# TA_2_DONG.net
KiCad netlist of a schematic drawn in EAGLE
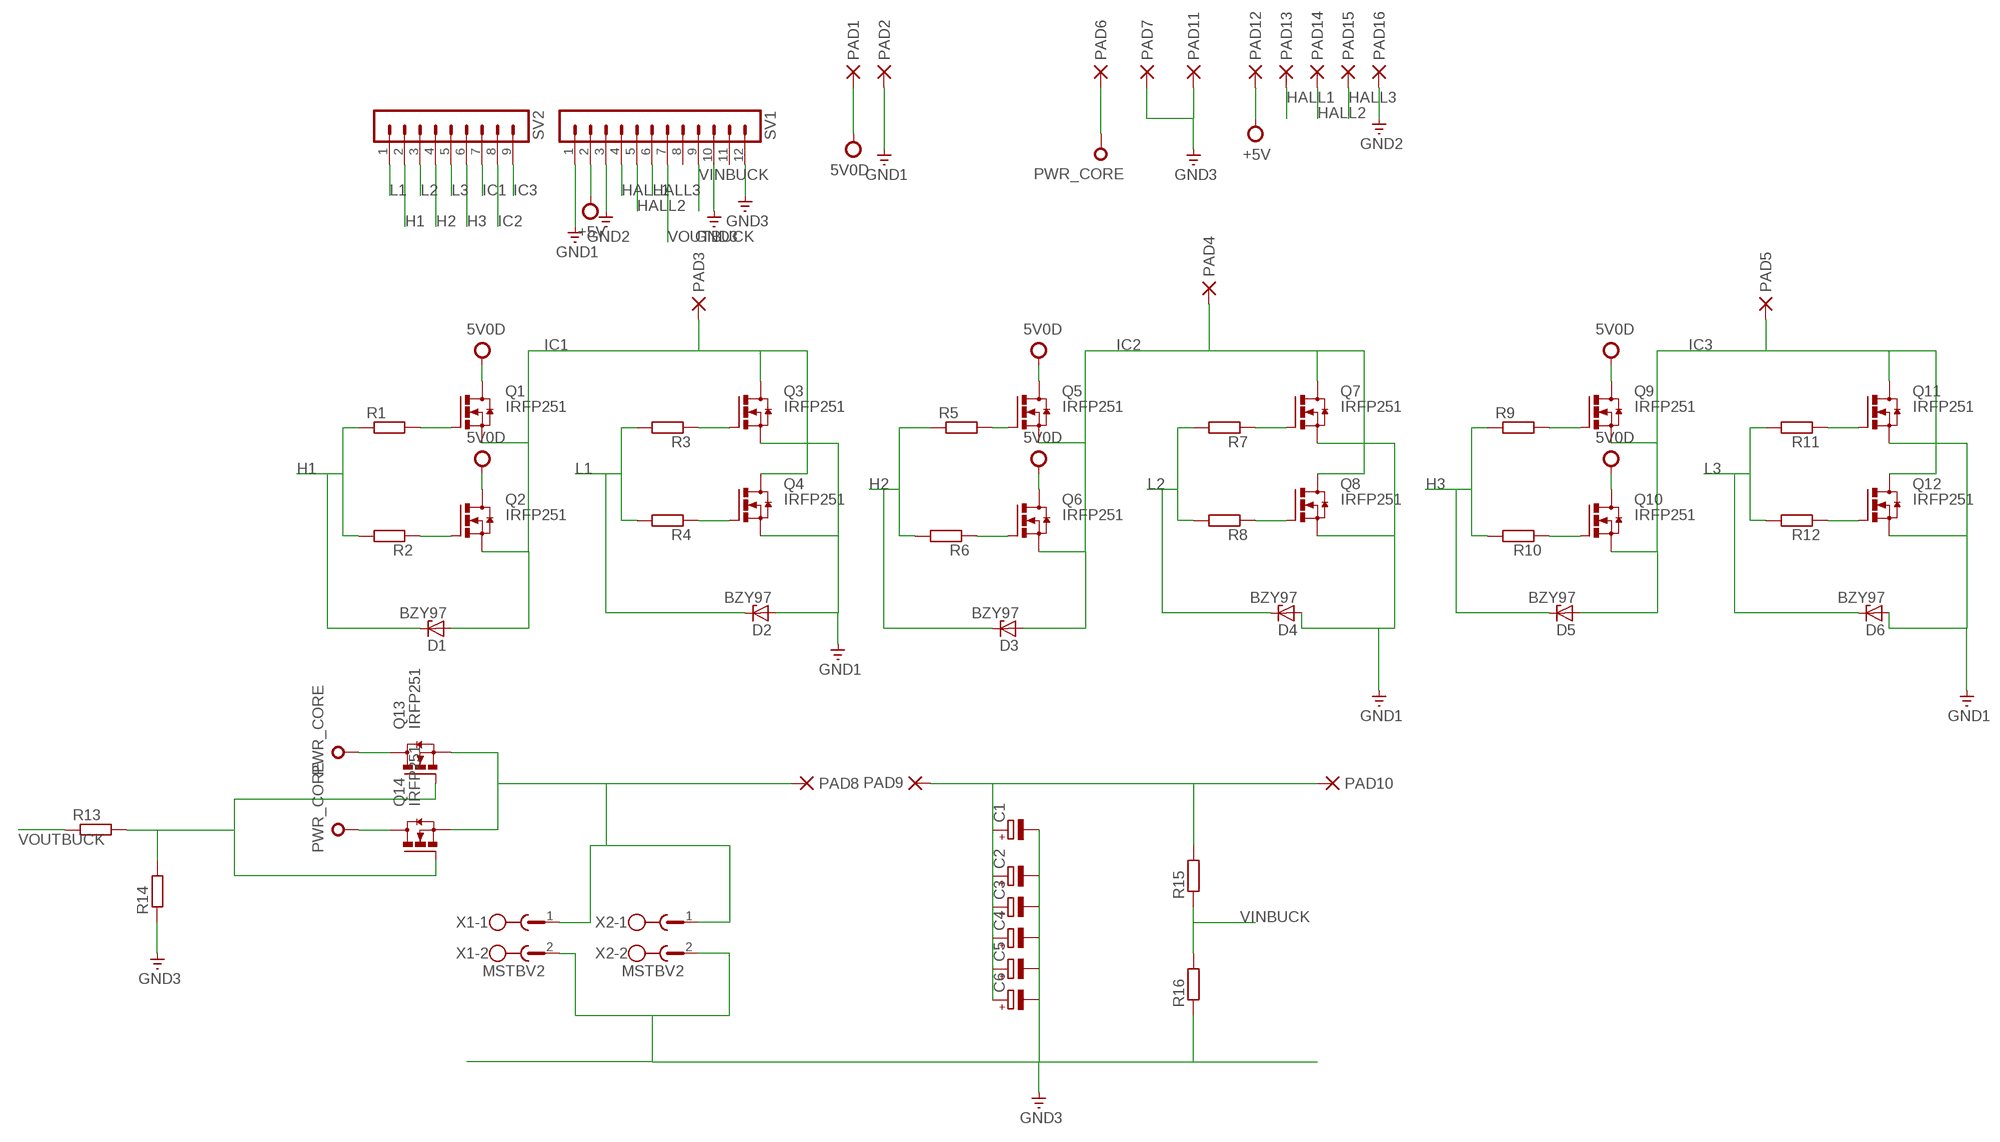
[diagram p0: schematic, sheet 1]

(export (version "E")
  (design (tool "Eeschema 10.0.6"))
  (components
    (comp (ref "C1")
      (value "CPOL-EUTT5D9")
      (footprint "eagle-import:TT5D9")
      (libsource (lib "eagle-import") (part "CPOL-EUTT5D9"))
    )
    (comp (ref "C2")
      (value "CPOL-EUTT5D9")
      (footprint "eagle-import:TT5D9")
      (libsource (lib "eagle-import") (part "CPOL-EUTT5D9"))
    )
    (comp (ref "C3")
      (value "CPOL-EUTT5D9")
      (footprint "eagle-import:TT5D9")
      (libsource (lib "eagle-import") (part "CPOL-EUTT5D9"))
    )
    (comp (ref "C4")
      (value "CPOL-EUTT5D9")
      (footprint "eagle-import:TT5D9")
      (libsource (lib "eagle-import") (part "CPOL-EUTT5D9"))
    )
    (comp (ref "C5")
      (value "CPOL-EUTT5D9")
      (footprint "eagle-import:TT5D9")
      (libsource (lib "eagle-import") (part "CPOL-EUTT5D9"))
    )
    (comp (ref "C6")
      (value "CPOL-EUTT5D9")
      (footprint "eagle-import:TT5D9")
      (libsource (lib "eagle-import") (part "CPOL-EUTT5D9"))
    )
    (comp (ref "D1")
      (value "BZY97")
      (footprint "eagle-import:F126Z12")
      (libsource (lib "eagle-import") (part "BZY97"))
    )
    (comp (ref "D2")
      (value "BZY97")
      (footprint "eagle-import:F126Z12")
      (libsource (lib "eagle-import") (part "BZY97"))
    )
    (comp (ref "D3")
      (value "BZY97")
      (footprint "eagle-import:F126Z12")
      (libsource (lib "eagle-import") (part "BZY97"))
    )
    (comp (ref "D4")
      (value "BZY97")
      (footprint "eagle-import:F126Z12")
      (libsource (lib "eagle-import") (part "BZY97"))
    )
    (comp (ref "D5")
      (value "BZY97")
      (footprint "eagle-import:F126Z12")
      (libsource (lib "eagle-import") (part "BZY97"))
    )
    (comp (ref "D6")
      (value "BZY97")
      (footprint "eagle-import:F126Z12")
      (libsource (lib "eagle-import") (part "BZY97"))
    )
    (comp (ref "PAD1")
      (value "PAD-0820")
      (footprint "eagle-import:0820")
      (libsource (lib "eagle-import") (part "PAD-0820"))
    )
    (comp (ref "PAD2")
      (value "PAD-0820")
      (footprint "eagle-import:0820")
      (libsource (lib "eagle-import") (part "PAD-0820"))
    )
    (comp (ref "PAD3")
      (value "PAD-0820")
      (footprint "eagle-import:0820")
      (libsource (lib "eagle-import") (part "PAD-0820"))
    )
    (comp (ref "PAD4")
      (value "PAD-0820")
      (footprint "eagle-import:0820")
      (libsource (lib "eagle-import") (part "PAD-0820"))
    )
    (comp (ref "PAD5")
      (value "PAD-0820")
      (footprint "eagle-import:0820")
      (libsource (lib "eagle-import") (part "PAD-0820"))
    )
    (comp (ref "PAD6")
      (value "PAD-0820")
      (footprint "eagle-import:0820")
      (libsource (lib "eagle-import") (part "PAD-0820"))
    )
    (comp (ref "PAD7")
      (value "PAD-0820")
      (footprint "eagle-import:0820")
      (libsource (lib "eagle-import") (part "PAD-0820"))
    )
    (comp (ref "PAD8")
      (value "PAD-0820")
      (footprint "eagle-import:0820")
      (libsource (lib "eagle-import") (part "PAD-0820"))
    )
    (comp (ref "PAD9")
      (value "PAD-0820")
      (footprint "eagle-import:0820")
      (libsource (lib "eagle-import") (part "PAD-0820"))
    )
    (comp (ref "PAD10")
      (value "PAD-0820")
      (footprint "eagle-import:0820")
      (libsource (lib "eagle-import") (part "PAD-0820"))
    )
    (comp (ref "PAD11")
      (value "PAD-0820")
      (footprint "eagle-import:0820")
      (libsource (lib "eagle-import") (part "PAD-0820"))
    )
    (comp (ref "PAD12")
      (value "PAD-0820")
      (footprint "eagle-import:0820")
      (libsource (lib "eagle-import") (part "PAD-0820"))
    )
    (comp (ref "PAD13")
      (value "PAD-0820")
      (footprint "eagle-import:0820")
      (libsource (lib "eagle-import") (part "PAD-0820"))
    )
    (comp (ref "PAD14")
      (value "PAD-0820")
      (footprint "eagle-import:0820")
      (libsource (lib "eagle-import") (part "PAD-0820"))
    )
    (comp (ref "PAD15")
      (value "PAD-0820")
      (footprint "eagle-import:0820")
      (libsource (lib "eagle-import") (part "PAD-0820"))
    )
    (comp (ref "PAD16")
      (value "PAD-0820")
      (footprint "eagle-import:0820")
      (libsource (lib "eagle-import") (part "PAD-0820"))
    )
    (comp (ref "Q1")
      (value "IRFP251")
      (footprint "eagle-import:TO-247AD-V")
      (libsource (lib "eagle-import") (part "IRFP251"))
    )
    (comp (ref "Q2")
      (value "IRFP251")
      (footprint "eagle-import:TO-247AD-V")
      (libsource (lib "eagle-import") (part "IRFP251"))
    )
    (comp (ref "Q3")
      (value "IRFP251")
      (footprint "eagle-import:TO-247AD-V")
      (libsource (lib "eagle-import") (part "IRFP251"))
    )
    (comp (ref "Q4")
      (value "IRFP251")
      (footprint "eagle-import:TO-247AD-V")
      (libsource (lib "eagle-import") (part "IRFP251"))
    )
    (comp (ref "Q5")
      (value "IRFP251")
      (footprint "eagle-import:TO-247AD-V")
      (libsource (lib "eagle-import") (part "IRFP251"))
    )
    (comp (ref "Q6")
      (value "IRFP251")
      (footprint "eagle-import:TO-247AD-V")
      (libsource (lib "eagle-import") (part "IRFP251"))
    )
    (comp (ref "Q7")
      (value "IRFP251")
      (footprint "eagle-import:TO-247AD-V")
      (libsource (lib "eagle-import") (part "IRFP251"))
    )
    (comp (ref "Q8")
      (value "IRFP251")
      (footprint "eagle-import:TO-247AD-V")
      (libsource (lib "eagle-import") (part "IRFP251"))
    )
    (comp (ref "Q9")
      (value "IRFP251")
      (footprint "eagle-import:TO-247AD-V")
      (libsource (lib "eagle-import") (part "IRFP251"))
    )
    (comp (ref "Q10")
      (value "IRFP251")
      (footprint "eagle-import:TO-247AD-V")
      (libsource (lib "eagle-import") (part "IRFP251"))
    )
    (comp (ref "Q11")
      (value "IRFP251")
      (footprint "eagle-import:TO-247AD-V")
      (libsource (lib "eagle-import") (part "IRFP251"))
    )
    (comp (ref "Q12")
      (value "IRFP251")
      (footprint "eagle-import:TO-247AD-V")
      (libsource (lib "eagle-import") (part "IRFP251"))
    )
    (comp (ref "Q13")
      (value "IRFP251")
      (footprint "eagle-import:TO-247AD-V")
      (libsource (lib "eagle-import") (part "IRFP251"))
    )
    (comp (ref "Q14")
      (value "IRFP251")
      (footprint "eagle-import:TO-247AD-V")
      (libsource (lib "eagle-import") (part "IRFP251"))
    )
    (comp (ref "R1")
      (value "R-EU_0207/15")
      (footprint "eagle-import:0207_15")
      (libsource (lib "eagle-import") (part "R-EU_0207/15"))
    )
    (comp (ref "R2")
      (value "R-EU_0207/15")
      (footprint "eagle-import:0207_15")
      (libsource (lib "eagle-import") (part "R-EU_0207/15"))
    )
    (comp (ref "R3")
      (value "R-EU_0207/15")
      (footprint "eagle-import:0207_15")
      (libsource (lib "eagle-import") (part "R-EU_0207/15"))
    )
    (comp (ref "R4")
      (value "R-EU_0207/15")
      (footprint "eagle-import:0207_15")
      (libsource (lib "eagle-import") (part "R-EU_0207/15"))
    )
    (comp (ref "R5")
      (value "R-EU_0207/15")
      (footprint "eagle-import:0207_15")
      (libsource (lib "eagle-import") (part "R-EU_0207/15"))
    )
    (comp (ref "R6")
      (value "R-EU_0207/15")
      (footprint "eagle-import:0207_15")
      (libsource (lib "eagle-import") (part "R-EU_0207/15"))
    )
    (comp (ref "R7")
      (value "R-EU_0207/15")
      (footprint "eagle-import:0207_15")
      (libsource (lib "eagle-import") (part "R-EU_0207/15"))
    )
    (comp (ref "R8")
      (value "R-EU_0207/15")
      (footprint "eagle-import:0207_15")
      (libsource (lib "eagle-import") (part "R-EU_0207/15"))
    )
    (comp (ref "R9")
      (value "R-EU_0207/15")
      (footprint "eagle-import:0207_15")
      (libsource (lib "eagle-import") (part "R-EU_0207/15"))
    )
    (comp (ref "R10")
      (value "R-EU_0207/15")
      (footprint "eagle-import:0207_15")
      (libsource (lib "eagle-import") (part "R-EU_0207/15"))
    )
    (comp (ref "R11")
      (value "R-EU_0207/15")
      (footprint "eagle-import:0207_15")
      (libsource (lib "eagle-import") (part "R-EU_0207/15"))
    )
    (comp (ref "R12")
      (value "R-EU_0207/15")
      (footprint "eagle-import:0207_15")
      (libsource (lib "eagle-import") (part "R-EU_0207/15"))
    )
    (comp (ref "R13")
      (value "R-EU_0207/15")
      (footprint "eagle-import:0207_15")
      (libsource (lib "eagle-import") (part "R-EU_0207/15"))
    )
    (comp (ref "R14")
      (value "R-EU_0207/15")
      (footprint "eagle-import:0207_15")
      (libsource (lib "eagle-import") (part "R-EU_0207/15"))
    )
    (comp (ref "R15")
      (value "R-EU_0207/15")
      (footprint "eagle-import:0207_15")
      (libsource (lib "eagle-import") (part "R-EU_0207/15"))
    )
    (comp (ref "R16")
      (value "R-EU_0207/15")
      (footprint "eagle-import:0207_15")
      (libsource (lib "eagle-import") (part "R-EU_0207/15"))
    )
    (comp (ref "SV1")
      (value "MA12-1")
      (footprint "eagle-import:MA12-1")
      (libsource (lib "eagle-import") (part "MA12-1"))
    )
    (comp (ref "SV2")
      (value "MA09-1")
      (footprint "eagle-import:MA09-1")
      (libsource (lib "eagle-import") (part "MA09-1"))
    )
    (comp (ref "X1")
      (value "MSTBV2")
      (footprint "eagle-import:MSTBV2")
      (fields (field (name "MPN") "MSTBV 2,5/2-GF-5.08"))
      (libsource (lib "eagle-import") (part "MSTBV2"))
    )
    (comp (ref "X2")
      (value "MSTBV2")
      (footprint "eagle-import:MSTBV2")
      (fields (field (name "MPN") "MSTBV 2,5/2-GF-5.08"))
      (libsource (lib "eagle-import") (part "MSTBV2"))
    )
  )
  (nets
    (net (code "1") (name "+5V") (class "Default")
      (node (ref "PAD12") (pin "P$1") (pinfunction "P_P$1") (pintype "passive"))
      (node (ref "SV1") (pin "2") (pinfunction "2_2") (pintype "passive"))
    )
    (net (code "2") (name "/H1") (class "Default")
      (node (ref "D1") (pin "C") (pinfunction "C_C") (pintype "passive"))
      (node (ref "R1") (pin "1") (pinfunction "1_1") (pintype "passive"))
      (node (ref "R2") (pin "2") (pinfunction "2_2") (pintype "passive"))
      (node (ref "SV2") (pin "2") (pinfunction "2_2") (pintype "passive"))
    )
    (net (code "3") (name "/H2") (class "Default")
      (node (ref "D3") (pin "C") (pinfunction "C_C") (pintype "passive"))
      (node (ref "R5") (pin "1") (pinfunction "1_1") (pintype "passive"))
      (node (ref "R6") (pin "2") (pinfunction "2_2") (pintype "passive"))
      (node (ref "SV2") (pin "4") (pinfunction "4_4") (pintype "passive"))
    )
    (net (code "4") (name "/H3") (class "Default")
      (node (ref "D5") (pin "C") (pinfunction "C_C") (pintype "passive"))
      (node (ref "R10") (pin "2") (pinfunction "2_2") (pintype "passive"))
      (node (ref "R9") (pin "1") (pinfunction "1_1") (pintype "passive"))
      (node (ref "SV2") (pin "6") (pinfunction "6_6") (pintype "passive"))
    )
    (net (code "5") (name "/HALL1") (class "Default")
      (node (ref "PAD13") (pin "P$1") (pinfunction "P_P$1") (pintype "passive"))
      (node (ref "SV1") (pin "4") (pinfunction "4_4") (pintype "passive"))
    )
    (net (code "6") (name "/HALL2") (class "Default")
      (node (ref "PAD14") (pin "P$1") (pinfunction "P_P$1") (pintype "passive"))
      (node (ref "SV1") (pin "5") (pinfunction "5_5") (pintype "passive"))
    )
    (net (code "7") (name "/HALL3") (class "Default")
      (node (ref "PAD15") (pin "P$1") (pinfunction "P_P$1") (pintype "passive"))
      (node (ref "SV1") (pin "6") (pinfunction "6_6") (pintype "passive"))
    )
    (net (code "8") (name "/IC1") (class "Default")
      (node (ref "D1") (pin "A") (pinfunction "A_A") (pintype "passive"))
      (node (ref "PAD3") (pin "P$1") (pinfunction "P_P$1") (pintype "passive"))
      (node (ref "Q1") (pin "S") (pinfunction "S_S") (pintype "passive"))
      (node (ref "Q2") (pin "S") (pinfunction "S_S") (pintype "passive"))
      (node (ref "Q3") (pin "D") (pinfunction "D_D") (pintype "passive"))
      (node (ref "Q4") (pin "D") (pinfunction "D_D") (pintype "passive"))
      (node (ref "SV2") (pin "7") (pinfunction "7_7") (pintype "passive"))
    )
    (net (code "9") (name "/IC2") (class "Default")
      (node (ref "D3") (pin "A") (pinfunction "A_A") (pintype "passive"))
      (node (ref "PAD4") (pin "P$1") (pinfunction "P_P$1") (pintype "passive"))
      (node (ref "Q5") (pin "S") (pinfunction "S_S") (pintype "passive"))
      (node (ref "Q6") (pin "S") (pinfunction "S_S") (pintype "passive"))
      (node (ref "Q7") (pin "D") (pinfunction "D_D") (pintype "passive"))
      (node (ref "Q8") (pin "D") (pinfunction "D_D") (pintype "passive"))
      (node (ref "SV2") (pin "8") (pinfunction "8_8") (pintype "passive"))
    )
    (net (code "10") (name "/IC3") (class "Default")
      (node (ref "D5") (pin "A") (pinfunction "A_A") (pintype "passive"))
      (node (ref "PAD5") (pin "P$1") (pinfunction "P_P$1") (pintype "passive"))
      (node (ref "Q10") (pin "S") (pinfunction "S_S") (pintype "passive"))
      (node (ref "Q11") (pin "D") (pinfunction "D_D") (pintype "passive"))
      (node (ref "Q12") (pin "D") (pinfunction "D_D") (pintype "passive"))
      (node (ref "Q9") (pin "S") (pinfunction "S_S") (pintype "passive"))
      (node (ref "SV2") (pin "9") (pinfunction "9_9") (pintype "passive"))
    )
    (net (code "11") (name "/L1") (class "Default")
      (node (ref "D2") (pin "C") (pinfunction "C_C") (pintype "passive"))
      (node (ref "R3") (pin "2") (pinfunction "2_2") (pintype "passive"))
      (node (ref "R4") (pin "2") (pinfunction "2_2") (pintype "passive"))
      (node (ref "SV2") (pin "1") (pinfunction "1_1") (pintype "passive"))
    )
    (net (code "12") (name "/L2") (class "Default")
      (node (ref "D4") (pin "C") (pinfunction "C_C") (pintype "passive"))
      (node (ref "R7") (pin "2") (pinfunction "2_2") (pintype "passive"))
      (node (ref "R8") (pin "2") (pinfunction "2_2") (pintype "passive"))
      (node (ref "SV2") (pin "3") (pinfunction "3_3") (pintype "passive"))
    )
    (net (code "13") (name "/L3") (class "Default")
      (node (ref "D6") (pin "C") (pinfunction "C_C") (pintype "passive"))
      (node (ref "R11") (pin "2") (pinfunction "2_2") (pintype "passive"))
      (node (ref "R12") (pin "2") (pinfunction "2_2") (pintype "passive"))
      (node (ref "SV2") (pin "5") (pinfunction "5_5") (pintype "passive"))
    )
    (net (code "14") (name "/VINBUCK") (class "Default")
      (node (ref "R15") (pin "1") (pinfunction "1_1") (pintype "passive"))
      (node (ref "R16") (pin "2") (pinfunction "2_2") (pintype "passive"))
      (node (ref "SV1") (pin "9") (pinfunction "9_9") (pintype "passive"))
    )
    (net (code "15") (name "/VOUTBUCK") (class "Default")
      (node (ref "R13") (pin "1") (pinfunction "1_1") (pintype "passive"))
      (node (ref "SV1") (pin "7") (pinfunction "7_7") (pintype "passive"))
    )
    (net (code "16") (name "5V0D") (class "Default")
      (node (ref "PAD1") (pin "P$1") (pinfunction "P_P$1") (pintype "passive"))
      (node (ref "Q1") (pin "D") (pinfunction "D_D") (pintype "passive"))
      (node (ref "Q10") (pin "D") (pinfunction "D_D") (pintype "passive"))
      (node (ref "Q2") (pin "D") (pinfunction "D_D") (pintype "passive"))
      (node (ref "Q5") (pin "D") (pinfunction "D_D") (pintype "passive"))
      (node (ref "Q6") (pin "D") (pinfunction "D_D") (pintype "passive"))
      (node (ref "Q9") (pin "D") (pinfunction "D_D") (pintype "passive"))
    )
    (net (code "17") (name "GND1") (class "Default")
      (node (ref "D2") (pin "A") (pinfunction "A_A") (pintype "passive"))
      (node (ref "D4") (pin "A") (pinfunction "A_A") (pintype "passive"))
      (node (ref "D6") (pin "A") (pinfunction "A_A") (pintype "passive"))
      (node (ref "PAD2") (pin "P$1") (pinfunction "P_P$1") (pintype "passive"))
      (node (ref "Q11") (pin "S") (pinfunction "S_S") (pintype "passive"))
      (node (ref "Q12") (pin "S") (pinfunction "S_S") (pintype "passive"))
      (node (ref "Q3") (pin "S") (pinfunction "S_S") (pintype "passive"))
      (node (ref "Q4") (pin "S") (pinfunction "S_S") (pintype "passive"))
      (node (ref "Q7") (pin "S") (pinfunction "S_S") (pintype "passive"))
      (node (ref "Q8") (pin "S") (pinfunction "S_S") (pintype "passive"))
      (node (ref "SV1") (pin "1") (pinfunction "1_1") (pintype "passive"))
    )
    (net (code "18") (name "GND2") (class "Default")
      (node (ref "PAD16") (pin "P$1") (pinfunction "P_P$1") (pintype "passive"))
      (node (ref "SV1") (pin "3") (pinfunction "3_3") (pintype "passive"))
    )
    (net (code "19") (name "GND3") (class "Default")
      (node (ref "C1") (pin "-") (pinfunction "-_-") (pintype "passive"))
      (node (ref "C2") (pin "-") (pinfunction "-_-") (pintype "passive"))
      (node (ref "C3") (pin "-") (pinfunction "-_-") (pintype "passive"))
      (node (ref "C4") (pin "-") (pinfunction "-_-") (pintype "passive"))
      (node (ref "C5") (pin "-") (pinfunction "-_-") (pintype "passive"))
      (node (ref "C6") (pin "-") (pinfunction "-_-") (pintype "passive"))
      (node (ref "PAD11") (pin "P$1") (pinfunction "P_P$1") (pintype "passive"))
      (node (ref "PAD7") (pin "P$1") (pinfunction "P_P$1") (pintype "passive"))
      (node (ref "R14") (pin "1") (pinfunction "1_1") (pintype "passive"))
      (node (ref "R16") (pin "1") (pinfunction "1_1") (pintype "passive"))
      (node (ref "SV1") (pin "10") (pinfunction "10_10") (pintype "passive"))
      (node (ref "SV1") (pin "12") (pinfunction "12_12") (pintype "passive"))
      (node (ref "X1") (pin "2") (pinfunction "1_2") (pintype "passive"))
      (node (ref "X2") (pin "2") (pinfunction "1_2") (pintype "passive"))
    )
    (net (code "20") (name "Net-(PAD8-P)") (class "Default")
      (node (ref "PAD8") (pin "P$1") (pinfunction "P_P$1") (pintype "passive"))
      (node (ref "Q13") (pin "S") (pinfunction "S_S") (pintype "passive"))
      (node (ref "Q14") (pin "S") (pinfunction "S_S") (pintype "passive"))
      (node (ref "X1") (pin "1") (pinfunction "1_1") (pintype "passive"))
      (node (ref "X2") (pin "1") (pinfunction "1_1") (pintype "passive"))
    )
    (net (code "21") (name "Net-(PAD10-P)") (class "Default")
      (node (ref "C1") (pin "+") (pinfunction "+_+") (pintype "passive"))
      (node (ref "C2") (pin "+") (pinfunction "+_+") (pintype "passive"))
      (node (ref "C3") (pin "+") (pinfunction "+_+") (pintype "passive"))
      (node (ref "C4") (pin "+") (pinfunction "+_+") (pintype "passive"))
      (node (ref "C5") (pin "+") (pinfunction "+_+") (pintype "passive"))
      (node (ref "C6") (pin "+") (pinfunction "+_+") (pintype "passive"))
      (node (ref "PAD10") (pin "P$1") (pinfunction "P_P$1") (pintype "passive"))
      (node (ref "PAD9") (pin "P$1") (pinfunction "P_P$1") (pintype "passive"))
      (node (ref "R15") (pin "2") (pinfunction "2_2") (pintype "passive"))
    )
    (net (code "22") (name "Net-(Q1-PadG)") (class "Default")
      (node (ref "Q1") (pin "G") (pinfunction "G_G") (pintype "passive"))
      (node (ref "R1") (pin "2") (pinfunction "2_2") (pintype "passive"))
    )
    (net (code "23") (name "Net-(Q2-PadG)") (class "Default")
      (node (ref "Q2") (pin "G") (pinfunction "G_G") (pintype "passive"))
      (node (ref "R2") (pin "1") (pinfunction "1_1") (pintype "passive"))
    )
    (net (code "24") (name "Net-(Q3-PadG)") (class "Default")
      (node (ref "Q3") (pin "G") (pinfunction "G_G") (pintype "passive"))
      (node (ref "R3") (pin "1") (pinfunction "1_1") (pintype "passive"))
    )
    (net (code "25") (name "Net-(Q4-PadG)") (class "Default")
      (node (ref "Q4") (pin "G") (pinfunction "G_G") (pintype "passive"))
      (node (ref "R4") (pin "1") (pinfunction "1_1") (pintype "passive"))
    )
    (net (code "26") (name "Net-(Q5-PadG)") (class "Default")
      (node (ref "Q5") (pin "G") (pinfunction "G_G") (pintype "passive"))
      (node (ref "R5") (pin "2") (pinfunction "2_2") (pintype "passive"))
    )
    (net (code "27") (name "Net-(Q6-PadG)") (class "Default")
      (node (ref "Q6") (pin "G") (pinfunction "G_G") (pintype "passive"))
      (node (ref "R6") (pin "1") (pinfunction "1_1") (pintype "passive"))
    )
    (net (code "28") (name "Net-(Q7-PadG)") (class "Default")
      (node (ref "Q7") (pin "G") (pinfunction "G_G") (pintype "passive"))
      (node (ref "R7") (pin "1") (pinfunction "1_1") (pintype "passive"))
    )
    (net (code "29") (name "Net-(Q8-PadG)") (class "Default")
      (node (ref "Q8") (pin "G") (pinfunction "G_G") (pintype "passive"))
      (node (ref "R8") (pin "1") (pinfunction "1_1") (pintype "passive"))
    )
    (net (code "30") (name "Net-(Q9-PadG)") (class "Default")
      (node (ref "Q9") (pin "G") (pinfunction "G_G") (pintype "passive"))
      (node (ref "R9") (pin "2") (pinfunction "2_2") (pintype "passive"))
    )
    (net (code "31") (name "Net-(Q10-PadG)") (class "Default")
      (node (ref "Q10") (pin "G") (pinfunction "G_G") (pintype "passive"))
      (node (ref "R10") (pin "1") (pinfunction "1_1") (pintype "passive"))
    )
    (net (code "32") (name "Net-(Q11-PadG)") (class "Default")
      (node (ref "Q11") (pin "G") (pinfunction "G_G") (pintype "passive"))
      (node (ref "R11") (pin "1") (pinfunction "1_1") (pintype "passive"))
    )
    (net (code "33") (name "Net-(Q12-PadG)") (class "Default")
      (node (ref "Q12") (pin "G") (pinfunction "G_G") (pintype "passive"))
      (node (ref "R12") (pin "1") (pinfunction "1_1") (pintype "passive"))
    )
    (net (code "34") (name "Net-(Q13-PadG)") (class "Default")
      (node (ref "Q13") (pin "G") (pinfunction "G_G") (pintype "passive"))
      (node (ref "Q14") (pin "G") (pinfunction "G_G") (pintype "passive"))
      (node (ref "R13") (pin "2") (pinfunction "2_2") (pintype "passive"))
      (node (ref "R14") (pin "2") (pinfunction "2_2") (pintype "passive"))
    )
    (net (code "35") (name "PWR_CORE") (class "Default")
      (node (ref "PAD6") (pin "P$1") (pinfunction "P_P$1") (pintype "passive"))
      (node (ref "Q13") (pin "D") (pinfunction "D_D") (pintype "passive"))
      (node (ref "Q14") (pin "D") (pinfunction "D_D") (pintype "passive"))
    )
    (net (code "36") (name "unconnected-(SV1-Pad8)") (class "Default")
      (node (ref "SV1") (pin "8") (pinfunction "8_8") (pintype "passive"))
    )
    (net (code "37") (name "unconnected-(SV1-Pad11)") (class "Default")
      (node (ref "SV1") (pin "11") (pinfunction "11_11") (pintype "passive"))
    )
  )
)
